# baseboard.net
KiCad netlist of a schematic drawn in EAGLE
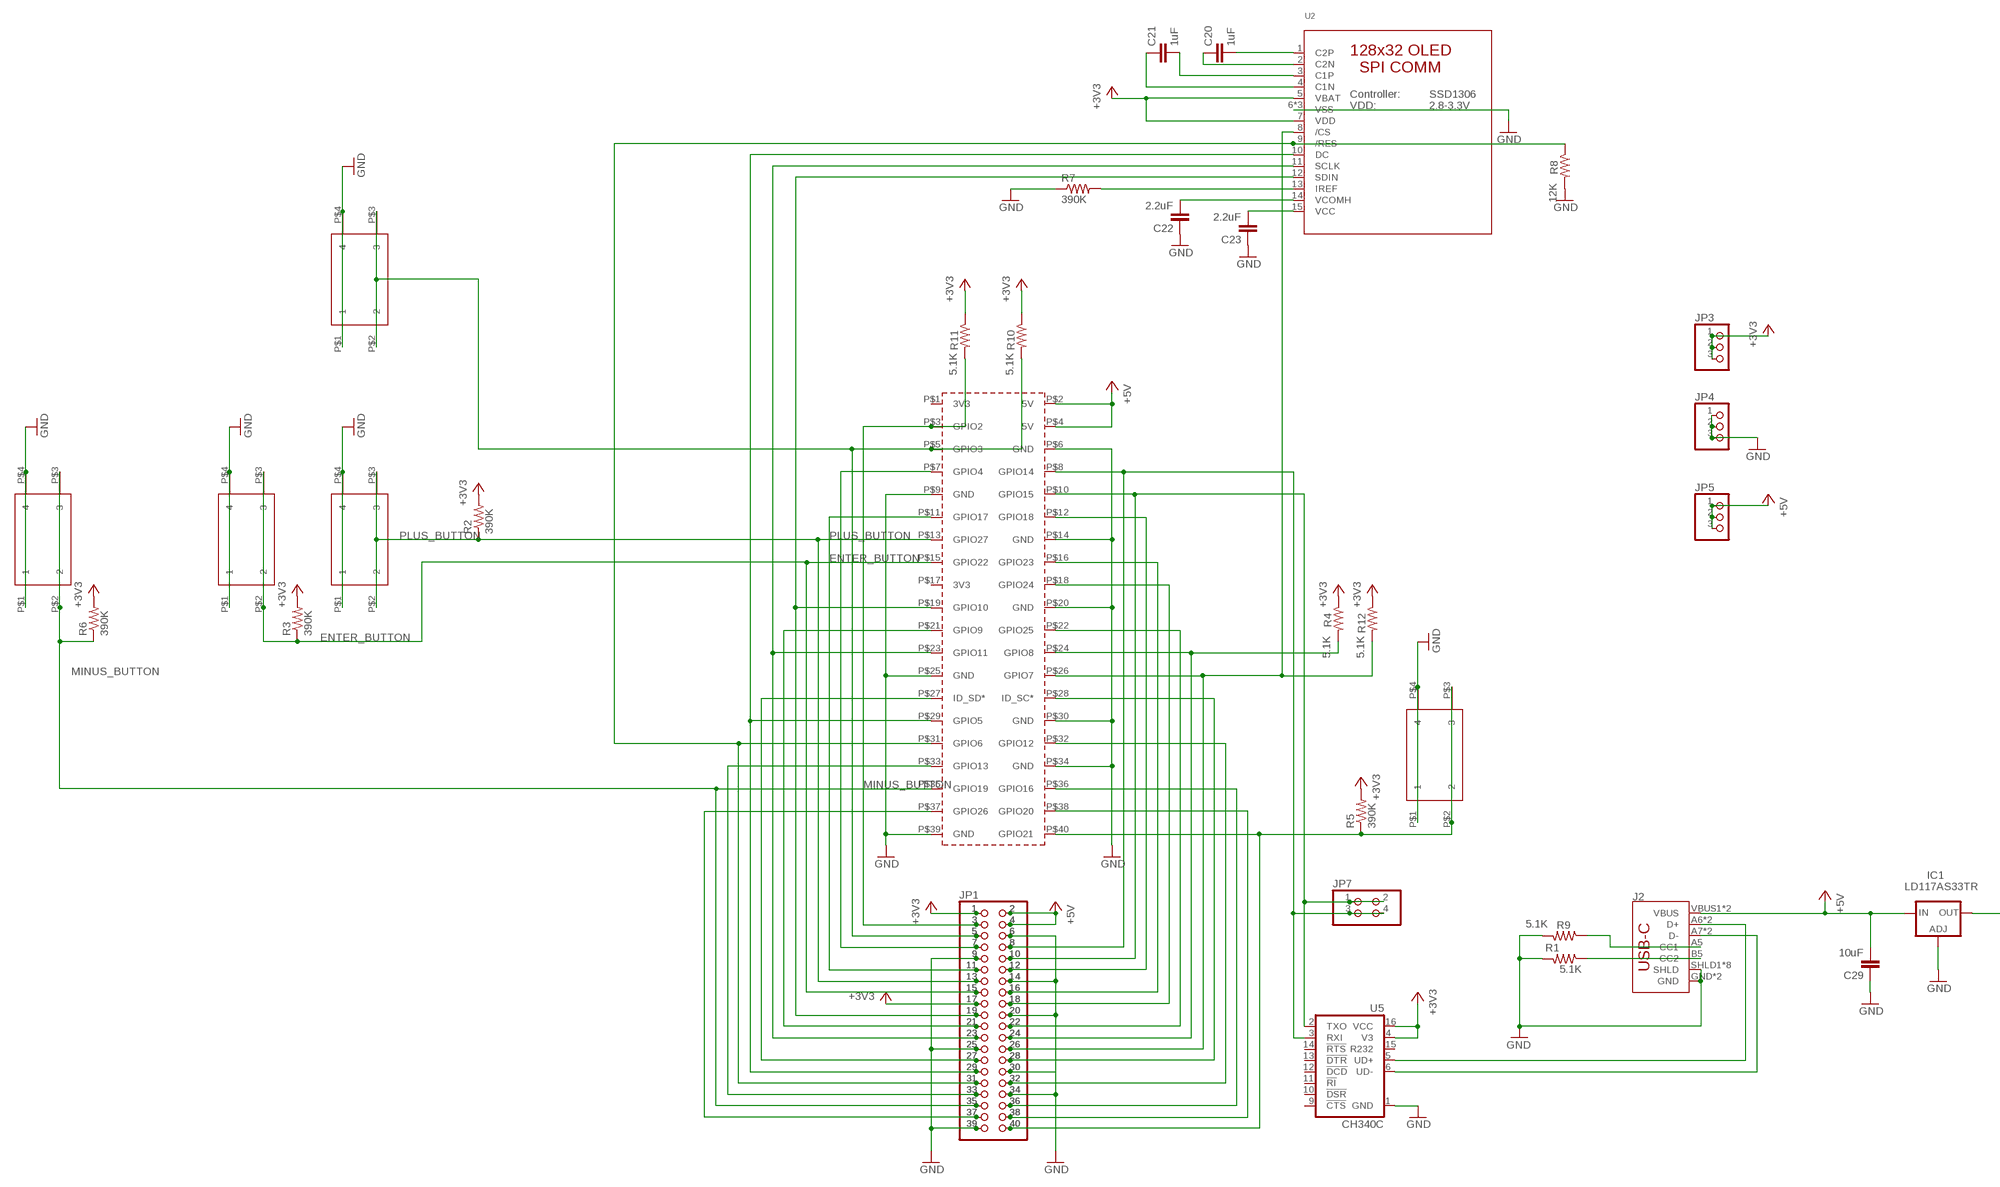
[diagram p0: schematic, sheet 1, part 1 of 2]
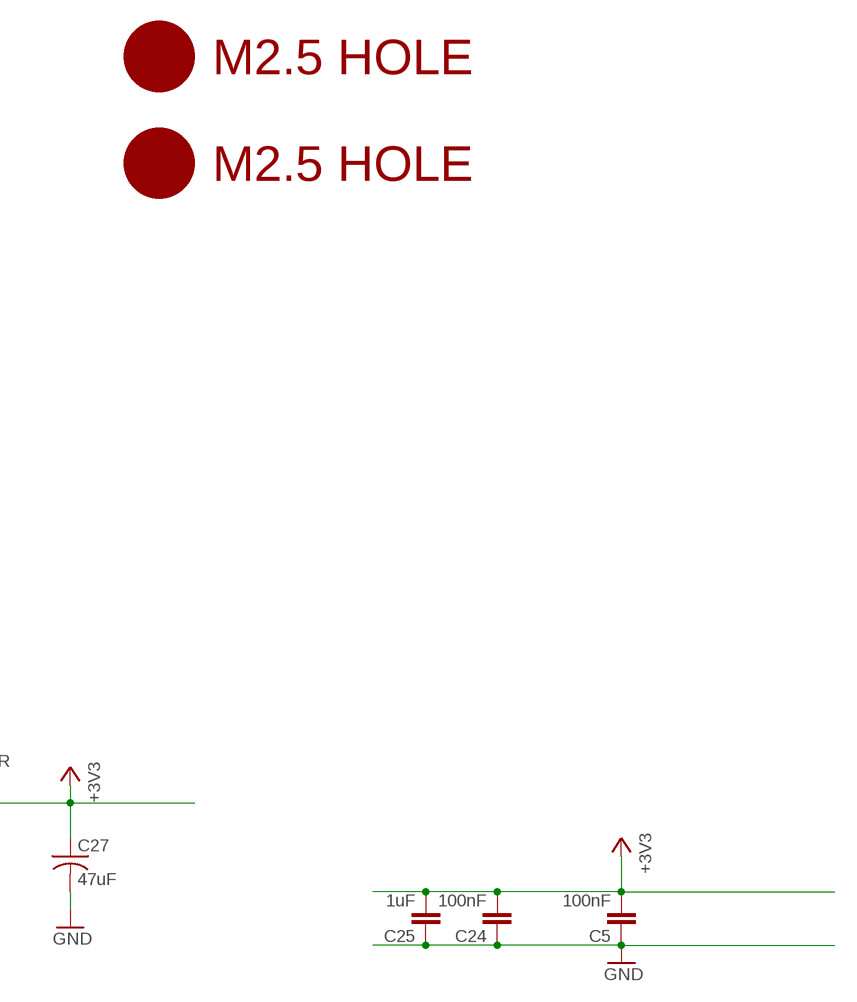
[diagram p1: schematic, sheet 1, part 2 of 2]

(export (version "E")
  (design (tool "Eeschema 10.0.6"))
  (components
    (comp (ref "C5")
      (value "100nF")
      (footprint "eagle-import:0805")
      (libsource (lib "eagle-import") (part "CAP0805"))
    )
    (comp (ref "C20")
      (value "1uF")
      (footprint "eagle-import:0805")
      (libsource (lib "eagle-import") (part "CAP0805"))
    )
    (comp (ref "C21")
      (value "1uF")
      (footprint "eagle-import:0805")
      (libsource (lib "eagle-import") (part "CAP0805"))
    )
    (comp (ref "C22")
      (value "2.2uF")
      (footprint "eagle-import:0805")
      (libsource (lib "eagle-import") (part "CAP0805"))
    )
    (comp (ref "C23")
      (value "2.2uF")
      (footprint "eagle-import:0805")
      (libsource (lib "eagle-import") (part "CAP0805"))
    )
    (comp (ref "C24")
      (value "100nF")
      (footprint "eagle-import:0805")
      (libsource (lib "eagle-import") (part "CAP0805"))
    )
    (comp (ref "C25")
      (value "1uF")
      (footprint "eagle-import:0805")
      (libsource (lib "eagle-import") (part "CAP0805"))
    )
    (comp (ref "C27")
      (value "47uF")
      (footprint "eagle-import:C1210")
      (libsource (lib "eagle-import") (part "C-USC1210"))
    )
    (comp (ref "C29")
      (value "10uF")
      (footprint "eagle-import:0805")
      (libsource (lib "eagle-import") (part "CAP0805"))
    )
    (comp (ref "IC1")
      (value "LD117AS33TR")
      (footprint "eagle-import:SOT223")
      (libsource (lib "eagle-import") (part "LD117A?S33TR"))
    )
    (comp (ref "J2")
      (value "USB_C16PIN")
      (footprint "eagle-import:USB-C-16P")
      (libsource (lib "eagle-import") (part "USB_C16PIN"))
    )
    (comp (ref "JP1")
      (value "PINHD-2X20-BIG")
      (footprint "eagle-import:2X20-BIG")
      (libsource (lib "eagle-import") (part "PINHD-2X20-BIG"))
    )
    (comp (ref "JP2")
      (value "PINHD-2X20-BIG")
      (footprint "eagle-import:2X20-BIG")
      (libsource (lib "eagle-import") (part "PINHD-2X20-BIG"))
    )
    (comp (ref "JP3")
      (value "PINHD-1X3")
      (footprint "eagle-import:1X03")
      (libsource (lib "eagle-import") (part "PINHD-1X3"))
    )
    (comp (ref "JP4")
      (value "PINHD-1X3")
      (footprint "eagle-import:1X03")
      (libsource (lib "eagle-import") (part "PINHD-1X3"))
    )
    (comp (ref "JP5")
      (value "PINHD-1X3")
      (footprint "eagle-import:1X03")
      (libsource (lib "eagle-import") (part "PINHD-1X3"))
    )
    (comp (ref "JP7")
      (value "PINHD-2X2")
      (footprint "eagle-import:2X02")
      (libsource (lib "eagle-import") (part "PINHD-2X2"))
    )
    (comp (ref "PCB1")
      (value "RPI3NO-CONNECTORS")
      (footprint "eagle-import:RPI3-NO-CONNECTORS")
      (libsource (lib "eagle-import") (part "RPI3NO-CONNECTORS"))
    )
    (comp (ref "R1")
      (value "5.1K")
      (footprint "eagle-import:0805")
      (libsource (lib "eagle-import") (part "joyAnalog_RESISTOR0805-RES"))
    )
    (comp (ref "R2")
      (value "390K")
      (footprint "eagle-import:0805")
      (libsource (lib "eagle-import") (part "RESISTOR0805-RES"))
    )
    (comp (ref "R3")
      (value "390K")
      (footprint "eagle-import:0805")
      (libsource (lib "eagle-import") (part "RESISTOR0805-RES"))
    )
    (comp (ref "R4")
      (value "5.1K")
      (footprint "eagle-import:0805")
      (libsource (lib "eagle-import") (part "joyAnalog_RESISTOR0805-RES"))
    )
    (comp (ref "R5")
      (value "390K")
      (footprint "eagle-import:0805")
      (libsource (lib "eagle-import") (part "RESISTOR0805-RES"))
    )
    (comp (ref "R6")
      (value "390K")
      (footprint "eagle-import:0805")
      (libsource (lib "eagle-import") (part "RESISTOR0805-RES"))
    )
    (comp (ref "R7")
      (value "390K")
      (footprint "eagle-import:0805")
      (libsource (lib "eagle-import") (part "RESISTOR0805-RES"))
    )
    (comp (ref "R8")
      (value "12K")
      (footprint "eagle-import:0805")
      (libsource (lib "eagle-import") (part "joyAnalog_RESISTOR0805-RES"))
    )
    (comp (ref "R9")
      (value "5.1K")
      (footprint "eagle-import:0805")
      (libsource (lib "eagle-import") (part "joyAnalog_RESISTOR0805-RES"))
    )
    (comp (ref "R10")
      (value "5.1K")
      (footprint "eagle-import:0805")
      (libsource (lib "eagle-import") (part "joyAnalog_RESISTOR0805-RES"))
    )
    (comp (ref "R11")
      (value "5.1K")
      (footprint "eagle-import:0805")
      (libsource (lib "eagle-import") (part "joyAnalog_RESISTOR0805-RES"))
    )
    (comp (ref "R12")
      (value "5.1K")
      (footprint "eagle-import:0805")
      (libsource (lib "eagle-import") (part "joyAnalog_RESISTOR0805-RES"))
    )
    (comp (ref "SW1")
      (value "324_SW")
      (footprint "eagle-import:342_SWICH_FOOT")
      (libsource (lib "eagle-import") (part "324_SW"))
    )
    (comp (ref "SW2")
      (value "324_SW")
      (footprint "eagle-import:342_SWICH_FOOT")
      (libsource (lib "eagle-import") (part "324_SW"))
    )
    (comp (ref "SW3")
      (value "324_SW")
      (footprint "eagle-import:342_SWICH_FOOT")
      (libsource (lib "eagle-import") (part "324_SW"))
    )
    (comp (ref "SW4")
      (value "324_SW")
      (footprint "eagle-import:342_SWICH_FOOT")
      (libsource (lib "eagle-import") (part "324_SW"))
    )
    (comp (ref "SW20")
      (value "324_SW")
      (footprint "eagle-import:342_SWICH_FOOT")
      (libsource (lib "eagle-import") (part "324_SW"))
    )
    (comp (ref "U$2")
      (value "M2.5HOLE")
      (footprint "eagle-import:M2.5HOLE")
      (libsource (lib "eagle-import") (part "M2.5HOLE"))
    )
    (comp (ref "U$3")
      (value "M2.5HOLE")
      (footprint "eagle-import:M2.5HOLE")
      (libsource (lib "eagle-import") (part "M2.5HOLE"))
    )
    (comp (ref "U2")
      (value "LUL_DISP_OLED_UG-2864HSWEG01")
      (footprint "eagle-import:LUL_UG-2864HSWEG01_1.3_WRAPAROUND")
      (libsource (lib "eagle-import") (part "LUL_DISP_OLED_UG-2864HSWEG01"))
    )
    (comp (ref "U5")
      (value "CH340C")
      (footprint "eagle-import:SO016")
      (libsource (lib "eagle-import") (part "CH340C"))
    )
  )
  (nets
    (net (code "1") (name "+3V3") (class "Default")
      (node (ref "C24") (pin "2") (pinfunction "2_2") (pintype "passive"))
      (node (ref "C25") (pin "2") (pinfunction "2_2") (pintype "passive"))
      (node (ref "C27") (pin "1") (pinfunction "1_1") (pintype "passive"))
      (node (ref "C5") (pin "2") (pinfunction "2_2") (pintype "passive"))
      (node (ref "IC1") (pin "4") (pinfunction "OUT_4") (pintype "passive"))
      (node (ref "JP1") (pin "1") (pinfunction "1_1") (pintype "passive"))
      (node (ref "JP1") (pin "17") (pinfunction "17_17") (pintype "passive"))
      (node (ref "JP2") (pin "1") (pinfunction "1_1") (pintype "passive"))
      (node (ref "JP2") (pin "17") (pinfunction "17_17") (pintype "passive"))
      (node (ref "JP3") (pin "1") (pinfunction "1_1") (pintype "passive"))
      (node (ref "JP3") (pin "2") (pinfunction "2_2") (pintype "passive"))
      (node (ref "JP3") (pin "3") (pinfunction "3_3") (pintype "passive"))
      (node (ref "R10") (pin "1") (pinfunction "1_1") (pintype "passive"))
      (node (ref "R11") (pin "1") (pinfunction "1_1") (pintype "passive"))
      (node (ref "R12") (pin "1") (pinfunction "1_1") (pintype "passive"))
      (node (ref "R2") (pin "2") (pinfunction "2_2") (pintype "passive"))
      (node (ref "R3") (pin "2") (pinfunction "2_2") (pintype "passive"))
      (node (ref "R4") (pin "1") (pinfunction "1_1") (pintype "passive"))
      (node (ref "R5") (pin "2") (pinfunction "2_2") (pintype "passive"))
      (node (ref "R6") (pin "2") (pinfunction "2_2") (pintype "passive"))
      (node (ref "U2") (pin "5") (pinfunction "VBAT_5") (pintype "input"))
      (node (ref "U2") (pin "7") (pinfunction "VDD_7") (pintype "power_in"))
      (node (ref "U5") (pin "16") (pinfunction "VCC_16") (pintype "bidirectional"))
      (node (ref "U5") (pin "4") (pinfunction "V3_4") (pintype "bidirectional"))
    )
    (net (code "2") (name "+5V") (class "Default")
      (node (ref "C29") (pin "2") (pinfunction "2_2") (pintype "passive"))
      (node (ref "IC1") (pin "3") (pinfunction "IN_3") (pintype "input"))
      (node (ref "J2") (pin "VBUS1") (pinfunction "VBUS_VBUS1") (pintype "bidirectional"))
      (node (ref "J2") (pin "VBUS2") (pinfunction "VBUS_VBUS2") (pintype "bidirectional"))
      (node (ref "JP1") (pin "2") (pinfunction "2_2") (pintype "passive"))
      (node (ref "JP1") (pin "4") (pinfunction "4_4") (pintype "passive"))
      (node (ref "JP2") (pin "2") (pinfunction "2_2") (pintype "passive"))
      (node (ref "JP2") (pin "4") (pinfunction "4_4") (pintype "passive"))
      (node (ref "JP5") (pin "1") (pinfunction "1_1") (pintype "passive"))
      (node (ref "JP5") (pin "2") (pinfunction "2_2") (pintype "passive"))
      (node (ref "JP5") (pin "3") (pinfunction "3_3") (pintype "passive"))
      (node (ref "PCB1") (pin "P$2") (pinfunction "5V_P$2") (pintype "bidirectional"))
      (node (ref "PCB1") (pin "P$4") (pinfunction "5V_P$4") (pintype "bidirectional"))
    )
    (net (code "3") (name "/ENTER_BUTTON") (class "Default")
      (node (ref "JP1") (pin "15") (pinfunction "15_15") (pintype "passive"))
      (node (ref "JP2") (pin "15") (pinfunction "15_15") (pintype "passive"))
      (node (ref "PCB1") (pin "P$15") (pinfunction "GPIO22_P$15") (pintype "bidirectional"))
      (node (ref "R3") (pin "1") (pinfunction "1_1") (pintype "passive"))
      (node (ref "SW20") (pin "P$2") (pinfunction "2_P$2") (pintype "bidirectional"))
      (node (ref "SW20") (pin "P$3") (pinfunction "3_P$3") (pintype "bidirectional"))
    )
    (net (code "4") (name "/MINUS_BUTTON") (class "Default")
      (node (ref "JP1") (pin "35") (pinfunction "35_35") (pintype "passive"))
      (node (ref "JP2") (pin "35") (pinfunction "35_35") (pintype "passive"))
      (node (ref "PCB1") (pin "P$35") (pinfunction "GPIO19_P$35") (pintype "bidirectional"))
      (node (ref "R6") (pin "1") (pinfunction "1_1") (pintype "passive"))
      (node (ref "SW4") (pin "P$2") (pinfunction "2_P$2") (pintype "bidirectional"))
      (node (ref "SW4") (pin "P$3") (pinfunction "3_P$3") (pintype "bidirectional"))
    )
    (net (code "5") (name "/PLUS_BUTTON") (class "Default")
      (node (ref "JP1") (pin "13") (pinfunction "13_13") (pintype "passive"))
      (node (ref "JP2") (pin "13") (pinfunction "13_13") (pintype "passive"))
      (node (ref "PCB1") (pin "P$13") (pinfunction "GPIO27_P$13") (pintype "bidirectional"))
      (node (ref "R2") (pin "1") (pinfunction "1_1") (pintype "passive"))
      (node (ref "SW1") (pin "P$2") (pinfunction "2_P$2") (pintype "bidirectional"))
      (node (ref "SW1") (pin "P$3") (pinfunction "3_P$3") (pintype "bidirectional"))
    )
    (net (code "6") (name "GND") (class "Default")
      (node (ref "C22") (pin "1") (pinfunction "1_1") (pintype "passive"))
      (node (ref "C23") (pin "1") (pinfunction "1_1") (pintype "passive"))
      (node (ref "C24") (pin "1") (pinfunction "1_1") (pintype "passive"))
      (node (ref "C25") (pin "1") (pinfunction "1_1") (pintype "passive"))
      (node (ref "C27") (pin "2") (pinfunction "2_2") (pintype "passive"))
      (node (ref "C29") (pin "1") (pinfunction "1_1") (pintype "passive"))
      (node (ref "C5") (pin "1") (pinfunction "1_1") (pintype "passive"))
      (node (ref "IC1") (pin "1") (pinfunction "ADJ_1") (pintype "input"))
      (node (ref "J2") (pin "GND") (pinfunction "GND_GND") (pintype "bidirectional"))
      (node (ref "J2") (pin "GND2") (pinfunction "GND_GND2") (pintype "bidirectional"))
      (node (ref "J2") (pin "SHLD1") (pinfunction "SHLD_SHLD1") (pintype "bidirectional"))
      (node (ref "J2") (pin "SHLD2") (pinfunction "SHLD_SHLD2") (pintype "bidirectional"))
      (node (ref "J2") (pin "SHLD3") (pinfunction "SHLD_SHLD3") (pintype "bidirectional"))
      (node (ref "J2") (pin "SHLD4") (pinfunction "SHLD_SHLD4") (pintype "bidirectional"))
      (node (ref "J2") (pin "SHLD5") (pinfunction "SHLD_SHLD5") (pintype "bidirectional"))
      (node (ref "J2") (pin "SHLD6") (pinfunction "SHLD_SHLD6") (pintype "bidirectional"))
      (node (ref "J2") (pin "SHLD7") (pinfunction "SHLD_SHLD7") (pintype "bidirectional"))
      (node (ref "J2") (pin "SHLD8") (pinfunction "SHLD_SHLD8") (pintype "bidirectional"))
      (node (ref "JP1") (pin "14") (pinfunction "14_14") (pintype "passive"))
      (node (ref "JP1") (pin "20") (pinfunction "20_20") (pintype "passive"))
      (node (ref "JP1") (pin "25") (pinfunction "25_25") (pintype "passive"))
      (node (ref "JP1") (pin "30") (pinfunction "30_30") (pintype "passive"))
      (node (ref "JP1") (pin "34") (pinfunction "34_34") (pintype "passive"))
      (node (ref "JP1") (pin "39") (pinfunction "39_39") (pintype "passive"))
      (node (ref "JP1") (pin "6") (pinfunction "6_6") (pintype "passive"))
      (node (ref "JP1") (pin "9") (pinfunction "9_9") (pintype "passive"))
      (node (ref "JP2") (pin "14") (pinfunction "14_14") (pintype "passive"))
      (node (ref "JP2") (pin "20") (pinfunction "20_20") (pintype "passive"))
      (node (ref "JP2") (pin "25") (pinfunction "25_25") (pintype "passive"))
      (node (ref "JP2") (pin "30") (pinfunction "30_30") (pintype "passive"))
      (node (ref "JP2") (pin "34") (pinfunction "34_34") (pintype "passive"))
      (node (ref "JP2") (pin "39") (pinfunction "39_39") (pintype "passive"))
      (node (ref "JP2") (pin "6") (pinfunction "6_6") (pintype "passive"))
      (node (ref "JP2") (pin "9") (pinfunction "9_9") (pintype "passive"))
      (node (ref "JP4") (pin "1") (pinfunction "1_1") (pintype "passive"))
      (node (ref "JP4") (pin "2") (pinfunction "2_2") (pintype "passive"))
      (node (ref "JP4") (pin "3") (pinfunction "3_3") (pintype "passive"))
      (node (ref "PCB1") (pin "P$14") (pinfunction "GND_P$14") (pintype "bidirectional"))
      (node (ref "PCB1") (pin "P$20") (pinfunction "GND_P$20") (pintype "bidirectional"))
      (node (ref "PCB1") (pin "P$25") (pinfunction "GND_P$25") (pintype "bidirectional"))
      (node (ref "PCB1") (pin "P$30") (pinfunction "GND_P$30") (pintype "bidirectional"))
      (node (ref "PCB1") (pin "P$34") (pinfunction "GND_P$34") (pintype "bidirectional"))
      (node (ref "PCB1") (pin "P$39") (pinfunction "GND_P$39") (pintype "bidirectional"))
      (node (ref "PCB1") (pin "P$6") (pinfunction "GND_P$6") (pintype "bidirectional"))
      (node (ref "PCB1") (pin "P$9") (pinfunction "GND_P$9") (pintype "bidirectional"))
      (node (ref "R1") (pin "2") (pinfunction "2_2") (pintype "passive"))
      (node (ref "R7") (pin "1") (pinfunction "1_1") (pintype "passive"))
      (node (ref "R8") (pin "2") (pinfunction "2_2") (pintype "passive"))
      (node (ref "R9") (pin "2") (pinfunction "2_2") (pintype "passive"))
      (node (ref "SW1") (pin "P$1") (pinfunction "1_P$1") (pintype "bidirectional"))
      (node (ref "SW1") (pin "P$4") (pinfunction "4_P$4") (pintype "bidirectional"))
      (node (ref "SW2") (pin "P$1") (pinfunction "1_P$1") (pintype "bidirectional"))
      (node (ref "SW2") (pin "P$4") (pinfunction "4_P$4") (pintype "bidirectional"))
      (node (ref "SW20") (pin "P$1") (pinfunction "1_P$1") (pintype "bidirectional"))
      (node (ref "SW20") (pin "P$4") (pinfunction "4_P$4") (pintype "bidirectional"))
      (node (ref "SW3") (pin "P$1") (pinfunction "1_P$1") (pintype "bidirectional"))
      (node (ref "SW3") (pin "P$4") (pinfunction "4_P$4") (pintype "bidirectional"))
      (node (ref "SW4") (pin "P$1") (pinfunction "1_P$1") (pintype "bidirectional"))
      (node (ref "SW4") (pin "P$4") (pinfunction "4_P$4") (pintype "bidirectional"))
      (node (ref "U2") (pin "16") (pinfunction "VSS_16") (pintype "power_in"))
      (node (ref "U2") (pin "17") (pinfunction "VSS_17") (pintype "power_in"))
      (node (ref "U2") (pin "6") (pinfunction "VSS_6") (pintype "power_in"))
      (node (ref "U5") (pin "1") (pinfunction "GND_1") (pintype "bidirectional"))
    )
    (net (code "7") (name "Net-(J2-CC1)") (class "Default")
      (node (ref "J2") (pin "A5") (pinfunction "CC1_A5") (pintype "bidirectional"))
      (node (ref "R9") (pin "1") (pinfunction "1_1") (pintype "passive"))
    )
    (net (code "8") (name "Net-(J2-CC2)") (class "Default")
      (node (ref "J2") (pin "B5") (pinfunction "CC2_B5") (pintype "bidirectional"))
      (node (ref "R1") (pin "1") (pinfunction "1_1") (pintype "passive"))
    )
    (net (code "9") (name "Net-(PCB1-GPIO2)") (class "Default")
      (node (ref "JP1") (pin "3") (pinfunction "3_3") (pintype "passive"))
      (node (ref "JP2") (pin "3") (pinfunction "3_3") (pintype "passive"))
      (node (ref "PCB1") (pin "P$3") (pinfunction "GPIO2_P$3") (pintype "bidirectional"))
      (node (ref "R11") (pin "2") (pinfunction "2_2") (pintype "passive"))
    )
    (net (code "10") (name "Net-(PCB1-GPIO3)") (class "Default")
      (node (ref "JP1") (pin "5") (pinfunction "5_5") (pintype "passive"))
      (node (ref "JP2") (pin "5") (pinfunction "5_5") (pintype "passive"))
      (node (ref "PCB1") (pin "P$5") (pinfunction "GPIO3_P$5") (pintype "bidirectional"))
      (node (ref "R10") (pin "2") (pinfunction "2_2") (pintype "passive"))
      (node (ref "SW2") (pin "P$2") (pinfunction "2_P$2") (pintype "bidirectional"))
      (node (ref "SW2") (pin "P$3") (pinfunction "3_P$3") (pintype "bidirectional"))
    )
    (net (code "11") (name "Net-(PCB1-GPIO4)") (class "Default")
      (node (ref "JP1") (pin "7") (pinfunction "7_7") (pintype "passive"))
      (node (ref "JP2") (pin "7") (pinfunction "7_7") (pintype "passive"))
      (node (ref "PCB1") (pin "P$7") (pinfunction "GPIO4_P$7") (pintype "bidirectional"))
    )
    (net (code "12") (name "Net-(PCB1-GPIO5)") (class "Default")
      (node (ref "JP1") (pin "29") (pinfunction "29_29") (pintype "passive"))
      (node (ref "JP2") (pin "29") (pinfunction "29_29") (pintype "passive"))
      (node (ref "PCB1") (pin "P$29") (pinfunction "GPIO5_P$29") (pintype "bidirectional"))
      (node (ref "U2") (pin "10") (pinfunction "DC_10") (pintype "input"))
    )
    (net (code "13") (name "Net-(PCB1-GPIO6)") (class "Default")
      (node (ref "JP1") (pin "31") (pinfunction "31_31") (pintype "passive"))
      (node (ref "JP2") (pin "31") (pinfunction "31_31") (pintype "passive"))
      (node (ref "PCB1") (pin "P$31") (pinfunction "GPIO6_P$31") (pintype "bidirectional"))
      (node (ref "R8") (pin "1") (pinfunction "1_1") (pintype "passive"))
      (node (ref "U2") (pin "9") (pinfunction "/RES_9") (pintype "input"))
    )
    (net (code "14") (name "Net-(PCB1-GPIO7)") (class "Default")
      (node (ref "JP1") (pin "26") (pinfunction "26_26") (pintype "passive"))
      (node (ref "JP2") (pin "26") (pinfunction "26_26") (pintype "passive"))
      (node (ref "PCB1") (pin "P$26") (pinfunction "GPIO7_P$26") (pintype "bidirectional"))
      (node (ref "R12") (pin "2") (pinfunction "2_2") (pintype "passive"))
      (node (ref "U2") (pin "8") (pinfunction "/CS_8") (pintype "input"))
    )
    (net (code "15") (name "Net-(PCB1-GPIO8)") (class "Default")
      (node (ref "JP1") (pin "24") (pinfunction "24_24") (pintype "passive"))
      (node (ref "JP2") (pin "24") (pinfunction "24_24") (pintype "passive"))
      (node (ref "PCB1") (pin "P$24") (pinfunction "GPIO8_P$24") (pintype "bidirectional"))
      (node (ref "R4") (pin "2") (pinfunction "2_2") (pintype "passive"))
    )
    (net (code "16") (name "Net-(PCB1-GPIO9)") (class "Default")
      (node (ref "JP1") (pin "21") (pinfunction "21_21") (pintype "passive"))
      (node (ref "JP2") (pin "21") (pinfunction "21_21") (pintype "passive"))
      (node (ref "PCB1") (pin "P$21") (pinfunction "GPIO9_P$21") (pintype "bidirectional"))
    )
    (net (code "17") (name "Net-(PCB1-GPIO10)") (class "Default")
      (node (ref "JP1") (pin "19") (pinfunction "19_19") (pintype "passive"))
      (node (ref "JP2") (pin "19") (pinfunction "19_19") (pintype "passive"))
      (node (ref "PCB1") (pin "P$19") (pinfunction "GPIO10_P$19") (pintype "bidirectional"))
      (node (ref "U2") (pin "12") (pinfunction "SDIN_12") (pintype "bidirectional"))
    )
    (net (code "18") (name "Net-(PCB1-GPIO11)") (class "Default")
      (node (ref "JP1") (pin "23") (pinfunction "23_23") (pintype "passive"))
      (node (ref "JP2") (pin "23") (pinfunction "23_23") (pintype "passive"))
      (node (ref "PCB1") (pin "P$23") (pinfunction "GPIO11_P$23") (pintype "bidirectional"))
      (node (ref "U2") (pin "11") (pinfunction "SCLK_11") (pintype "bidirectional"))
    )
    (net (code "19") (name "Net-(PCB1-GPIO12)") (class "Default")
      (node (ref "JP1") (pin "32") (pinfunction "32_32") (pintype "passive"))
      (node (ref "JP2") (pin "32") (pinfunction "32_32") (pintype "passive"))
      (node (ref "PCB1") (pin "P$32") (pinfunction "GPIO12_P$32") (pintype "bidirectional"))
    )
    (net (code "20") (name "Net-(PCB1-GPIO13)") (class "Default")
      (node (ref "JP1") (pin "33") (pinfunction "33_33") (pintype "passive"))
      (node (ref "JP2") (pin "33") (pinfunction "33_33") (pintype "passive"))
      (node (ref "PCB1") (pin "P$33") (pinfunction "GPIO13_P$33") (pintype "bidirectional"))
    )
    (net (code "21") (name "Net-(PCB1-GPIO14)") (class "Default")
      (node (ref "JP1") (pin "8") (pinfunction "8_8") (pintype "passive"))
      (node (ref "JP2") (pin "8") (pinfunction "8_8") (pintype "passive"))
      (node (ref "JP7") (pin "3") (pinfunction "3_3") (pintype "passive"))
      (node (ref "JP7") (pin "4") (pinfunction "4_4") (pintype "passive"))
      (node (ref "PCB1") (pin "P$8") (pinfunction "GPIO14_P$8") (pintype "bidirectional"))
      (node (ref "U5") (pin "3") (pinfunction "RXI_3") (pintype "bidirectional"))
    )
    (net (code "22") (name "Net-(PCB1-GPIO15)") (class "Default")
      (node (ref "JP1") (pin "10") (pinfunction "10_10") (pintype "passive"))
      (node (ref "JP2") (pin "10") (pinfunction "10_10") (pintype "passive"))
      (node (ref "JP7") (pin "1") (pinfunction "1_1") (pintype "passive"))
      (node (ref "JP7") (pin "2") (pinfunction "2_2") (pintype "passive"))
      (node (ref "PCB1") (pin "P$10") (pinfunction "GPIO15_P$10") (pintype "bidirectional"))
      (node (ref "U5") (pin "2") (pinfunction "TXO_2") (pintype "bidirectional"))
    )
    (net (code "23") (name "Net-(PCB1-GPIO16)") (class "Default")
      (node (ref "JP1") (pin "36") (pinfunction "36_36") (pintype "passive"))
      (node (ref "JP2") (pin "36") (pinfunction "36_36") (pintype "passive"))
      (node (ref "PCB1") (pin "P$36") (pinfunction "GPIO16_P$36") (pintype "bidirectional"))
    )
    (net (code "24") (name "Net-(PCB1-GPIO17)") (class "Default")
      (node (ref "JP1") (pin "11") (pinfunction "11_11") (pintype "passive"))
      (node (ref "JP2") (pin "11") (pinfunction "11_11") (pintype "passive"))
      (node (ref "PCB1") (pin "P$11") (pinfunction "GPIO17_P$11") (pintype "bidirectional"))
    )
    (net (code "25") (name "Net-(PCB1-GPIO18)") (class "Default")
      (node (ref "JP1") (pin "12") (pinfunction "12_12") (pintype "passive"))
      (node (ref "JP2") (pin "12") (pinfunction "12_12") (pintype "passive"))
      (node (ref "PCB1") (pin "P$12") (pinfunction "GPIO18_P$12") (pintype "bidirectional"))
    )
    (net (code "26") (name "Net-(PCB1-GPIO20)") (class "Default")
      (node (ref "JP1") (pin "38") (pinfunction "38_38") (pintype "passive"))
      (node (ref "JP2") (pin "38") (pinfunction "38_38") (pintype "passive"))
      (node (ref "PCB1") (pin "P$38") (pinfunction "GPIO20_P$38") (pintype "bidirectional"))
    )
    (net (code "27") (name "Net-(PCB1-GPIO21)") (class "Default")
      (node (ref "JP1") (pin "40") (pinfunction "40_40") (pintype "passive"))
      (node (ref "JP2") (pin "40") (pinfunction "40_40") (pintype "passive"))
      (node (ref "PCB1") (pin "P$40") (pinfunction "GPIO21_P$40") (pintype "bidirectional"))
      (node (ref "R5") (pin "1") (pinfunction "1_1") (pintype "passive"))
      (node (ref "SW3") (pin "P$2") (pinfunction "2_P$2") (pintype "bidirectional"))
      (node (ref "SW3") (pin "P$3") (pinfunction "3_P$3") (pintype "bidirectional"))
    )
    (net (code "28") (name "Net-(PCB1-GPIO23)") (class "Default")
      (node (ref "JP1") (pin "16") (pinfunction "16_16") (pintype "passive"))
      (node (ref "JP2") (pin "16") (pinfunction "16_16") (pintype "passive"))
      (node (ref "PCB1") (pin "P$16") (pinfunction "GPIO23_P$16") (pintype "bidirectional"))
    )
    (net (code "29") (name "Net-(PCB1-GPIO24)") (class "Default")
      (node (ref "JP1") (pin "18") (pinfunction "18_18") (pintype "passive"))
      (node (ref "JP2") (pin "18") (pinfunction "18_18") (pintype "passive"))
      (node (ref "PCB1") (pin "P$18") (pinfunction "GPIO24_P$18") (pintype "bidirectional"))
    )
    (net (code "30") (name "Net-(PCB1-GPIO25)") (class "Default")
      (node (ref "JP1") (pin "22") (pinfunction "22_22") (pintype "passive"))
      (node (ref "JP2") (pin "22") (pinfunction "22_22") (pintype "passive"))
      (node (ref "PCB1") (pin "P$22") (pinfunction "GPIO25_P$22") (pintype "bidirectional"))
    )
    (net (code "31") (name "Net-(PCB1-GPIO26)") (class "Default")
      (node (ref "JP1") (pin "37") (pinfunction "37_37") (pintype "passive"))
      (node (ref "JP2") (pin "37") (pinfunction "37_37") (pintype "passive"))
      (node (ref "PCB1") (pin "P$37") (pinfunction "GPIO26_P$37") (pintype "bidirectional"))
    )
    (net (code "32") (name "Net-(PCB1-ID_SC*)") (class "Default")
      (node (ref "JP1") (pin "28") (pinfunction "28_28") (pintype "passive"))
      (node (ref "JP2") (pin "28") (pinfunction "28_28") (pintype "passive"))
      (node (ref "PCB1") (pin "P$28") (pinfunction "ID_SC*_P$28") (pintype "bidirectional"))
    )
    (net (code "33") (name "Net-(PCB1-ID_SD*)") (class "Default")
      (node (ref "JP1") (pin "27") (pinfunction "27_27") (pintype "passive"))
      (node (ref "JP2") (pin "27") (pinfunction "27_27") (pintype "passive"))
      (node (ref "PCB1") (pin "P$27") (pinfunction "ID_SD*_P$27") (pintype "bidirectional"))
    )
    (net (code "34") (name "Net-(U2-C1N)") (class "Default")
      (node (ref "C21") (pin "1") (pinfunction "1_1") (pintype "passive"))
      (node (ref "U2") (pin "4") (pinfunction "C1N_4") (pintype "input"))
    )
    (net (code "35") (name "Net-(U2-C1P)") (class "Default")
      (node (ref "C21") (pin "2") (pinfunction "2_2") (pintype "passive"))
      (node (ref "U2") (pin "3") (pinfunction "C1P_3") (pintype "input"))
    )
    (net (code "36") (name "Net-(U2-C2N)") (class "Default")
      (node (ref "C20") (pin "1") (pinfunction "1_1") (pintype "passive"))
      (node (ref "U2") (pin "2") (pinfunction "C2N_2") (pintype "input"))
    )
    (net (code "37") (name "Net-(U2-C2P)") (class "Default")
      (node (ref "C20") (pin "2") (pinfunction "2_2") (pintype "passive"))
      (node (ref "U2") (pin "1") (pinfunction "C2P_1") (pintype "input"))
    )
    (net (code "38") (name "Net-(U2-IREF)") (class "Default")
      (node (ref "R7") (pin "2") (pinfunction "2_2") (pintype "passive"))
      (node (ref "U2") (pin "13") (pinfunction "IREF_13") (pintype "input"))
    )
    (net (code "39") (name "Net-(U2-VCC)") (class "Default")
      (node (ref "C23") (pin "2") (pinfunction "2_2") (pintype "passive"))
      (node (ref "U2") (pin "15") (pinfunction "VCC_15") (pintype "power_in"))
    )
    (net (code "40") (name "Net-(U2-VCOMH)") (class "Default")
      (node (ref "C22") (pin "2") (pinfunction "2_2") (pintype "passive"))
      (node (ref "U2") (pin "14") (pinfunction "VCOMH_14") (pintype "output"))
    )
    (net (code "41") (name "Net-(U5-UD+)") (class "Default")
      (node (ref "J2") (pin "A6") (pinfunction "D+_A6") (pintype "bidirectional"))
      (node (ref "J2") (pin "B6") (pinfunction "D+_B6") (pintype "bidirectional"))
      (node (ref "U5") (pin "5") (pinfunction "UD+_5") (pintype "bidirectional"))
    )
    (net (code "42") (name "Net-(U5-UD-)") (class "Default")
      (node (ref "J2") (pin "A7") (pinfunction "D-_A7") (pintype "bidirectional"))
      (node (ref "J2") (pin "B7") (pinfunction "D-_B7") (pintype "bidirectional"))
      (node (ref "U5") (pin "6") (pinfunction "UD-_6") (pintype "bidirectional"))
    )
    (net (code "43") (name "unconnected-(PCB1-3V3-PadP$1)") (class "Default")
      (node (ref "PCB1") (pin "P$1") (pinfunction "3V3_P$1") (pintype "bidirectional"))
    )
    (net (code "44") (name "unconnected-(PCB1-3V3-PadP$17)") (class "Default")
      (node (ref "PCB1") (pin "P$17") (pinfunction "3V3_P$17") (pintype "bidirectional"))
    )
    (net (code "45") (name "unconnected-(U5-R232-Pad15)") (class "Default")
      (node (ref "U5") (pin "15") (pinfunction "R232_15") (pintype "bidirectional"))
    )
    (net (code "46") (name "unconnected-(U5-~{CTS}-Pad9)") (class "Default")
      (node (ref "U5") (pin "9") (pinfunction "~{CTS}_9") (pintype "bidirectional"))
    )
    (net (code "47") (name "unconnected-(U5-~{DCD}-Pad12)") (class "Default")
      (node (ref "U5") (pin "12") (pinfunction "~{DCD}_12") (pintype "bidirectional"))
    )
    (net (code "48") (name "unconnected-(U5-~{DSR}-Pad10)") (class "Default")
      (node (ref "U5") (pin "10") (pinfunction "~{DSR}_10") (pintype "bidirectional"))
    )
    (net (code "49") (name "unconnected-(U5-~{DTR}-Pad13)") (class "Default")
      (node (ref "U5") (pin "13") (pinfunction "~{DTR}_13") (pintype "bidirectional"))
    )
    (net (code "50") (name "unconnected-(U5-~{RI}-Pad11)") (class "Default")
      (node (ref "U5") (pin "11") (pinfunction "~{RI}_11") (pintype "bidirectional"))
    )
    (net (code "51") (name "unconnected-(U5-~{RTS}-Pad14)") (class "Default")
      (node (ref "U5") (pin "14") (pinfunction "~{RTS}_14") (pintype "bidirectional"))
    )
  )
)
